# SV601272A-ADC.net
KiCad netlist of a schematic drawn in Altium Designer
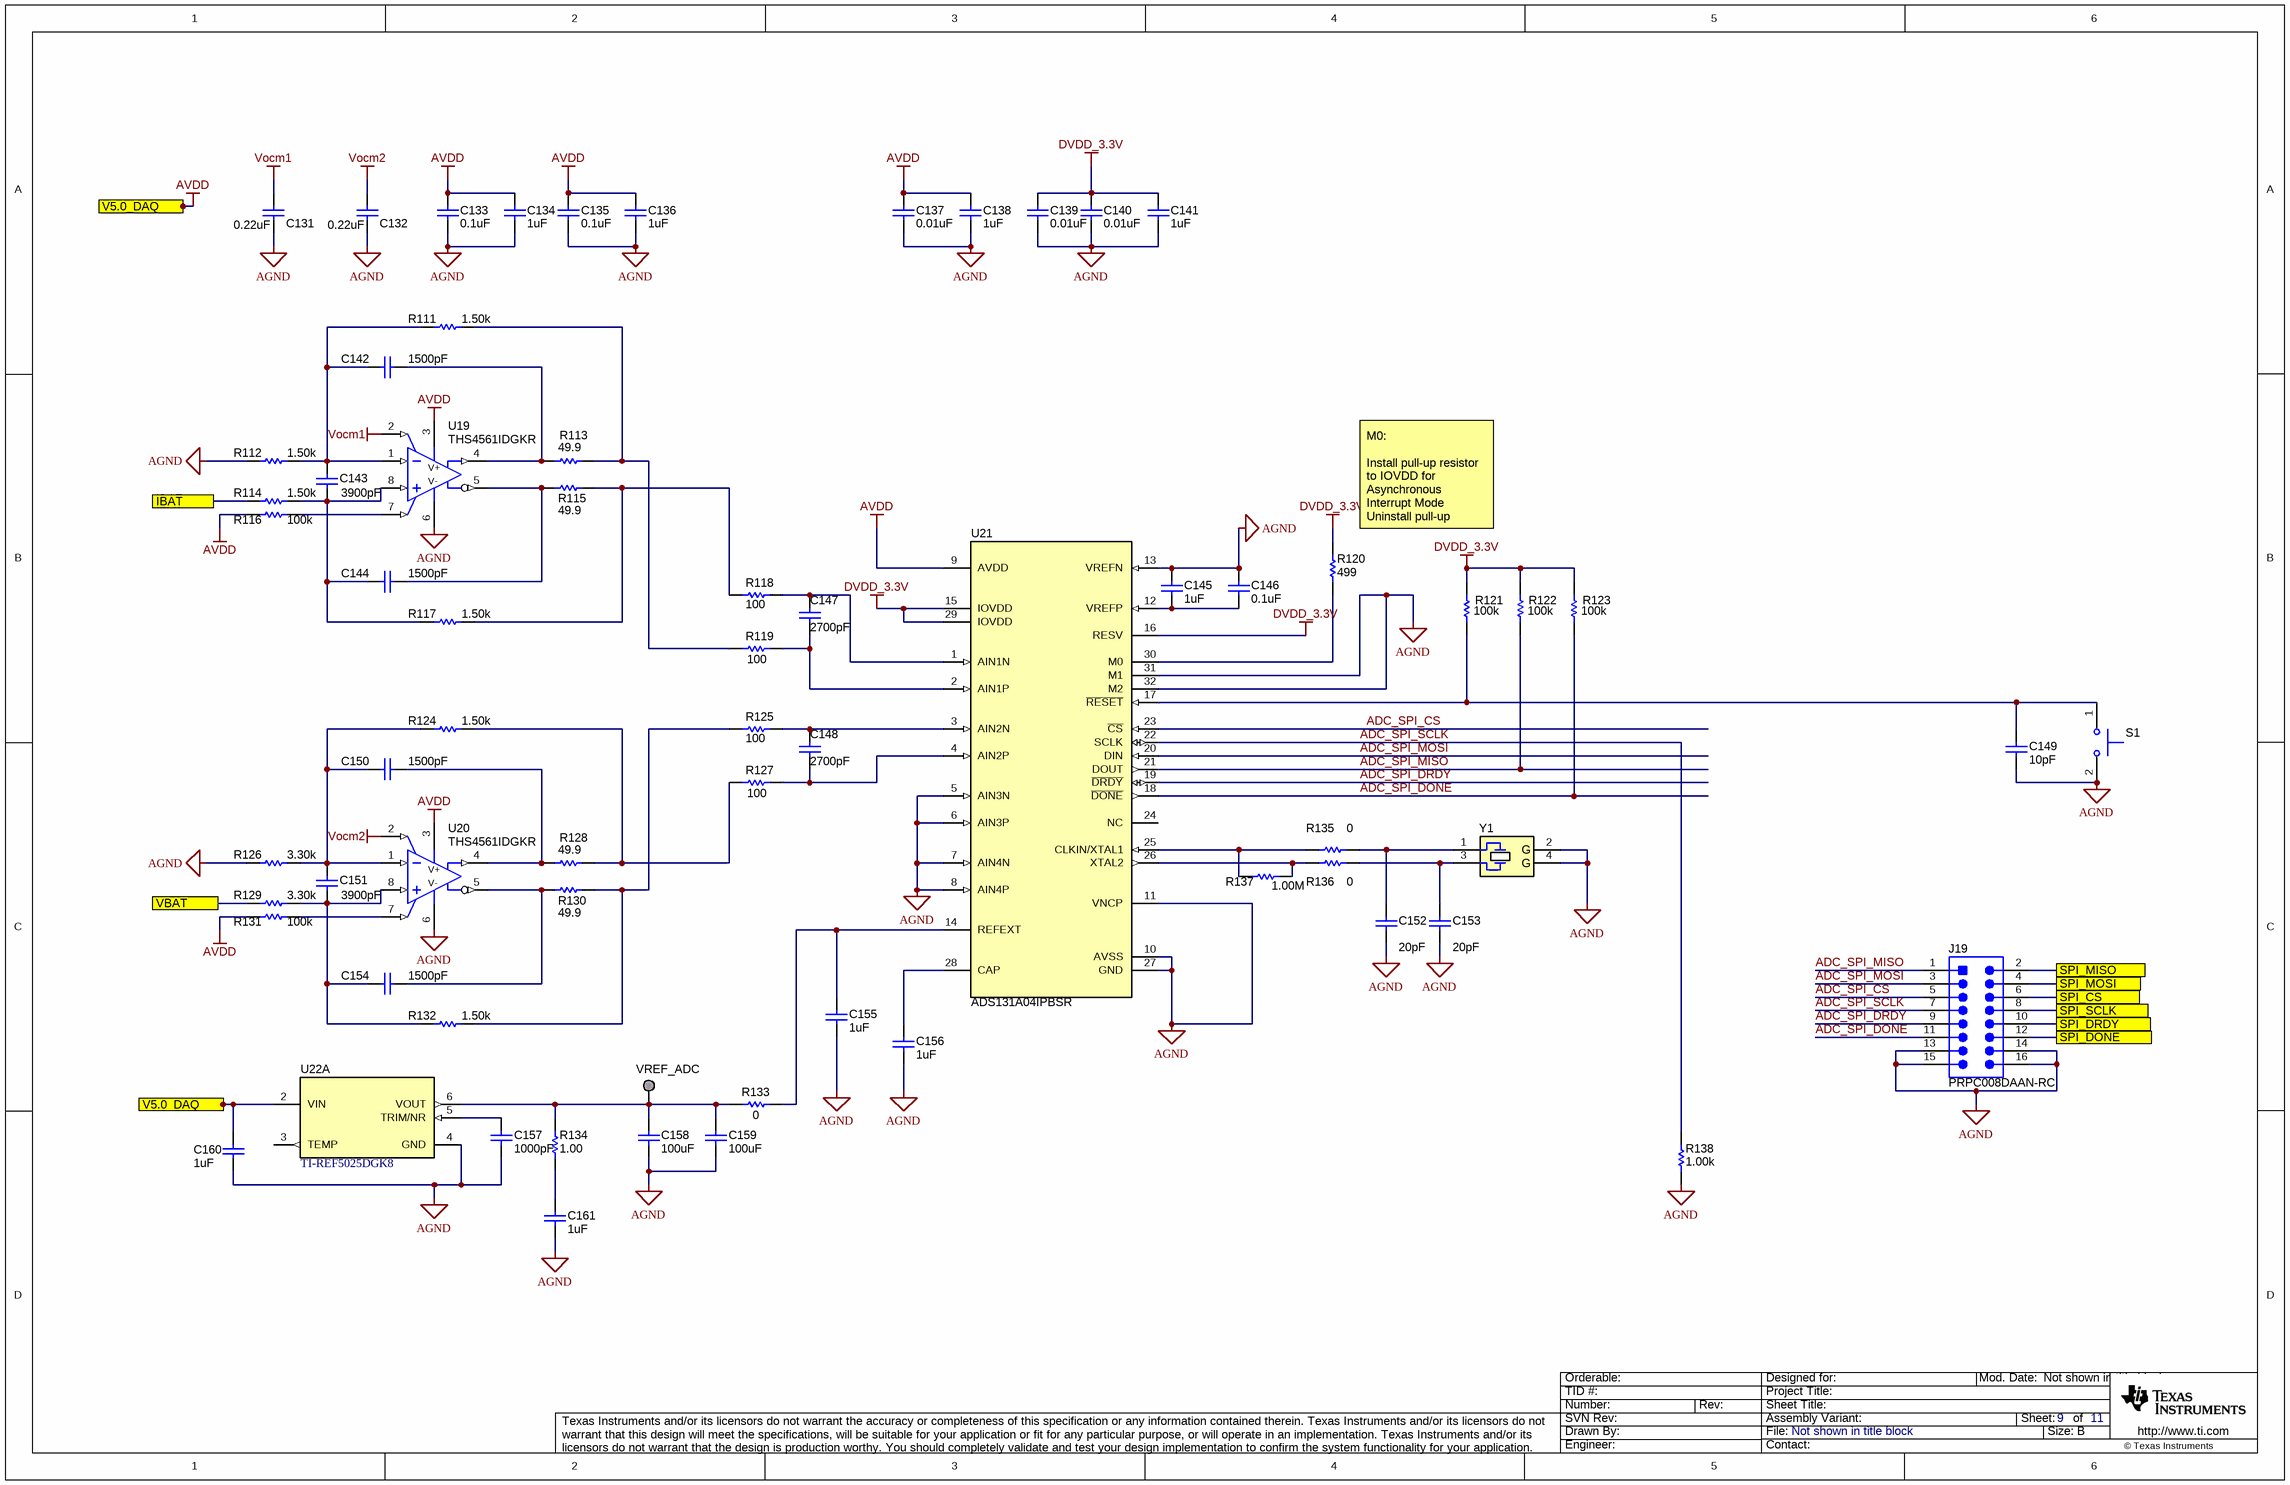
[diagram p0: SV601272A-ADC.SchDoc]

(export (version "E")
  (design (tool "Eeschema 10.0.6"))
  (components
    (comp (ref "C131")
      (value "Capacitor")
      (footprint "0603")
      (description "CAP, CERM, 0.22 uF, 16 V, +/- 10%, X7R, 0603")
      (fields
        (field (name "PARTNUMBER") "C0603C224K4RACTU")
        (field (name "VALUEDISPLAYED") "0.22uF")
        (field (name "MANUFACTURER") "Kemet")
        (field (name "PUBLISHER") "Texas Instruments")
      )
      (libsource (lib "Altium Vault - TI") (part "CMP-0006903-4"))
    )
    (comp (ref "C132")
      (value "Capacitor")
      (footprint "0603")
      (description "CAP, CERM, 0.22 uF, 16 V, +/- 10%, X7R, 0603")
      (fields
        (field (name "PARTNUMBER") "C0603C224K4RACTU")
        (field (name "VALUEDISPLAYED") "0.22uF")
        (field (name "MANUFACTURER") "Kemet")
        (field (name "PUBLISHER") "Texas Instruments")
      )
      (libsource (lib "Altium Vault - TI") (part "CMP-0006903-4"))
    )
    (comp (ref "C133")
      (value "Capacitor")
      (footprint "0603")
      (description "CAP, CERM, 0.1 uF, 25 V, +/- 5%, X7R, 0603")
      (fields
        (field (name "PARTNUMBER") "06033C104JAT2A")
        (field (name "VALUEDISPLAYED") "0.1uF")
        (field (name "MANUFACTURER") "AVX")
        (field (name "PUBLISHER") "Texas Instruments")
      )
      (libsource (lib "Altium Vault - TI") (part "CMP-0006752-5"))
    )
    (comp (ref "C134")
      (value "Capacitor")
      (footprint "0603")
      (description "CAP, CERM, 1 uF, 25 V, +/- 10%, X7R, 0603")
      (fields
        (field (name "PARTNUMBER") "GRM188R71E105KA12D")
        (field (name "VALUEDISPLAYED") "1uF")
        (field (name "MANUFACTURER") "MuRata")
        (field (name "PUBLISHER") "Texas Instruments")
      )
      (libsource (lib "Altium Vault - TI") (part "CMP-0007405-4"))
    )
    (comp (ref "C135")
      (value "Capacitor")
      (footprint "0603")
      (description "CAP, CERM, 0.1 uF, 25 V, +/- 5%, X7R, 0603")
      (fields
        (field (name "PARTNUMBER") "06033C104JAT2A")
        (field (name "VALUEDISPLAYED") "0.1uF")
        (field (name "MANUFACTURER") "AVX")
        (field (name "PUBLISHER") "Texas Instruments")
      )
      (libsource (lib "Altium Vault - TI") (part "CMP-0006752-5"))
    )
    (comp (ref "C136")
      (value "Capacitor")
      (footprint "0603")
      (description "CAP, CERM, 1 uF, 25 V, +/- 10%, X7R, 0603")
      (fields
        (field (name "PARTNUMBER") "GRM188R71E105KA12D")
        (field (name "VALUEDISPLAYED") "1uF")
        (field (name "MANUFACTURER") "MuRata")
        (field (name "PUBLISHER") "Texas Instruments")
      )
      (libsource (lib "Altium Vault - TI") (part "CMP-0007405-4"))
    )
    (comp (ref "C137")
      (value "Capacitor")
      (footprint "0603")
      (description "CAP, CERM, 0.01 uF, 100 V, +/- 10%, X7R, 0603")
      (fields
        (field (name "PARTNUMBER") "06031C103KAT2A")
        (field (name "VALUEDISPLAYED") "0.01uF")
        (field (name "MANUFACTURER") "AVX")
        (field (name "PUBLISHER") "Texas Instruments")
      )
      (libsource (lib "Altium Vault - TI") (part "CMP-0006727-4"))
    )
    (comp (ref "C138")
      (value "Capacitor")
      (footprint "0603")
      (description "CAP, CERM, 1 uF, 25 V, +/- 10%, X7R, 0603")
      (fields
        (field (name "PARTNUMBER") "GRM188R71E105KA12D")
        (field (name "VALUEDISPLAYED") "1uF")
        (field (name "MANUFACTURER") "MuRata")
        (field (name "PUBLISHER") "Texas Instruments")
      )
      (libsource (lib "Altium Vault - TI") (part "CMP-0007405-4"))
    )
    (comp (ref "C139")
      (value "Capacitor")
      (footprint "0603")
      (description "CAP, CERM, 0.01 uF, 100 V, +/- 10%, X7R, 0603")
      (fields
        (field (name "PARTNUMBER") "06031C103KAT2A")
        (field (name "VALUEDISPLAYED") "0.01uF")
        (field (name "MANUFACTURER") "AVX")
        (field (name "PUBLISHER") "Texas Instruments")
      )
      (libsource (lib "Altium Vault - TI") (part "CMP-0006727-4"))
    )
    (comp (ref "C140")
      (value "Capacitor")
      (footprint "0603")
      (description "CAP, CERM, 0.01 uF, 100 V, +/- 10%, X7R, 0603")
      (fields
        (field (name "PARTNUMBER") "06031C103KAT2A")
        (field (name "VALUEDISPLAYED") "0.01uF")
        (field (name "MANUFACTURER") "AVX")
        (field (name "PUBLISHER") "Texas Instruments")
      )
      (libsource (lib "Altium Vault - TI") (part "CMP-0006727-4"))
    )
    (comp (ref "C141")
      (value "Capacitor")
      (footprint "0603")
      (description "CAP, CERM, 1 uF, 25 V, +/- 10%, X7R, 0603")
      (fields
        (field (name "PARTNUMBER") "GRM188R71E105KA12D")
        (field (name "VALUEDISPLAYED") "1uF")
        (field (name "MANUFACTURER") "MuRata")
        (field (name "PUBLISHER") "Texas Instruments")
      )
      (libsource (lib "Altium Vault - TI") (part "CMP-0007405-4"))
    )
    (comp (ref "C142")
      (value "Capacitor")
      (footprint "0603")
      (description "CAP, CERM, 1500 pF, 100 V, +/- 5%, X7R, 0603")
      (fields
        (field (name "PARTNUMBER") "06031C152JAT2A")
        (field (name "VALUEDISPLAYED") "1500pF")
        (field (name "MANUFACTURER") "AVX")
        (field (name "PUBLISHER") "Texas Instruments")
      )
      (libsource (lib "Altium Vault - TI") (part "Capacitor"))
    )
    (comp (ref "C143")
      (value "GRM188R72A392KA01D")
      (footprint "0603")
      (description "CAP, CERM, 3900 pF, 100 V, +/- 10%, X7R, 0603")
      (fields
        (field (name "MANUFACTURER") "MuRata")
        (field (name "VALUEDISPLAYED") "3900pF")
        (field (name "PUBLISHER") "Texas Instruments")
      )
      (libsource (lib "Altium Vault - TI") (part "CMP-0007481-5"))
    )
    (comp (ref "C144")
      (value "Capacitor")
      (footprint "0603")
      (description "CAP, CERM, 1500 pF, 100 V, +/- 5%, X7R, 0603")
      (fields
        (field (name "PARTNUMBER") "06031C152JAT2A")
        (field (name "VALUEDISPLAYED") "1500pF")
        (field (name "MANUFACTURER") "AVX")
        (field (name "PUBLISHER") "Texas Instruments")
      )
      (libsource (lib "Altium Vault - TI") (part "Capacitor"))
    )
    (comp (ref "C145")
      (value "Capacitor")
      (footprint "0603")
      (description "CAP, CERM, 1 uF, 25 V, +/- 10%, X7R, 0603")
      (fields
        (field (name "PARTNUMBER") "GRM188R71E105KA12D")
        (field (name "VALUEDISPLAYED") "1uF")
        (field (name "MANUFACTURER") "MuRata")
        (field (name "PUBLISHER") "Texas Instruments")
      )
      (libsource (lib "Altium Vault - TI") (part "Capacitor"))
    )
    (comp (ref "C146")
      (value "Capacitor")
      (footprint "0603")
      (description "CAP, CERM, 0.1 uF, 25 V, +/- 5%, X7R, 0603")
      (fields
        (field (name "PARTNUMBER") "06033C104JAT2A")
        (field (name "VALUEDISPLAYED") "0.1uF")
        (field (name "MANUFACTURER") "AVX")
        (field (name "PUBLISHER") "Texas Instruments")
      )
      (libsource (lib "Altium Vault - TI") (part "Capacitor"))
    )
    (comp (ref "C147")
      (value "Capacitor")
      (footprint "0603")
      (description "CAP, CERM, 2700 pF, 50 V, +/- 5%, C0G/NP0, 0603")
      (fields
        (field (name "PARTNUMBER") "GRM1885C1H272JA01D")
        (field (name "VALUEDISPLAYED") "2700pF")
        (field (name "MANUFACTURER") "MuRata")
        (field (name "PUBLISHER") "Texas Instruments")
      )
      (libsource (lib "Altium Vault - TI") (part "Capacitor"))
    )
    (comp (ref "C148")
      (value "Capacitor")
      (footprint "0603")
      (description "CAP, CERM, 2700 pF, 50 V, +/- 5%, C0G/NP0, 0603")
      (fields
        (field (name "PARTNUMBER") "GRM1885C1H272JA01D")
        (field (name "VALUEDISPLAYED") "2700pF")
        (field (name "MANUFACTURER") "MuRata")
        (field (name "PUBLISHER") "Texas Instruments")
      )
      (libsource (lib "Altium Vault - TI") (part "Capacitor"))
    )
    (comp (ref "C149")
      (value "Capacitor")
      (footprint "0603")
      (description "CAP, CERM, 10 pF, 50 V, +/- 5%, C0G/NP0, 0603")
      (fields
        (field (name "PARTNUMBER") "06035A100JAT2A")
        (field (name "VALUEDISPLAYED") "10pF")
        (field (name "MANUFACTURER") "AVX")
        (field (name "PUBLISHER") "Texas Instruments")
      )
      (libsource (lib "Altium Vault - TI") (part "Capacitor"))
    )
    (comp (ref "C150")
      (value "Capacitor")
      (footprint "0603")
      (description "CAP, CERM, 1500 pF, 100 V, +/- 5%, X7R, 0603")
      (fields
        (field (name "PARTNUMBER") "06031C152JAT2A")
        (field (name "VALUEDISPLAYED") "1500pF")
        (field (name "MANUFACTURER") "AVX")
        (field (name "PUBLISHER") "Texas Instruments")
      )
      (libsource (lib "Altium Vault - TI") (part "Capacitor"))
    )
    (comp (ref "C151")
      (value "GRM188R72A392KA01D")
      (footprint "0603")
      (description "CAP, CERM, 3900 pF, 100 V, +/- 10%, X7R, 0603")
      (fields
        (field (name "MANUFACTURER") "MuRata")
        (field (name "VALUEDISPLAYED") "3900pF")
        (field (name "PUBLISHER") "Texas Instruments")
      )
      (libsource (lib "Altium Vault - TI") (part "CMP-0007481-5"))
    )
    (comp (ref "C152")
      (value "GRM1885C1H200JA01D")
      (footprint "0603")
      (description "CAP, CERM, 20 pF, 50 V, +/- 5%, C0G/NP0, 0603")
      (fields
        (field (name "MANUFACTURER") "MuRata")
        (field (name "VALUEDISPLAYED") "20pF")
        (field (name "PUBLISHER") "Texas Instruments")
      )
      (libsource (lib "Altium Vault - TI") (part "CMP-0007193-4"))
    )
    (comp (ref "C153")
      (value "GRM1885C1H200JA01D")
      (footprint "0603")
      (description "CAP, CERM, 20 pF, 50 V, +/- 5%, C0G/NP0, 0603")
      (fields
        (field (name "MANUFACTURER") "MuRata")
        (field (name "VALUEDISPLAYED") "20pF")
        (field (name "PUBLISHER") "Texas Instruments")
      )
      (libsource (lib "Altium Vault - TI") (part "CMP-0007193-4"))
    )
    (comp (ref "C154")
      (value "Capacitor")
      (footprint "0603")
      (description "CAP, CERM, 1500 pF, 100 V, +/- 5%, X7R, 0603")
      (fields
        (field (name "PARTNUMBER") "06031C152JAT2A")
        (field (name "VALUEDISPLAYED") "1500pF")
        (field (name "MANUFACTURER") "AVX")
        (field (name "PUBLISHER") "Texas Instruments")
      )
      (libsource (lib "Altium Vault - TI") (part "Capacitor"))
    )
    (comp (ref "C155")
      (value "Capacitor")
      (footprint "0603")
      (description "CAP, CERM, 1 uF, 25 V, +/- 10%, X7R, 0603")
      (fields
        (field (name "PARTNUMBER") "GRM188R71E105KA12D")
        (field (name "VALUEDISPLAYED") "1uF")
        (field (name "MANUFACTURER") "MuRata")
        (field (name "PUBLISHER") "Texas Instruments")
      )
      (libsource (lib "Altium Vault - TI") (part "Capacitor"))
    )
    (comp (ref "C156")
      (value "Capacitor")
      (footprint "0603")
      (description "CAP, CERM, 1 uF, 25 V, +/- 10%, X7R, 0603")
      (fields
        (field (name "PARTNUMBER") "GRM188R71E105KA12D")
        (field (name "VALUEDISPLAYED") "1uF")
        (field (name "MANUFACTURER") "MuRata")
        (field (name "PUBLISHER") "Texas Instruments")
      )
      (libsource (lib "Altium Vault - TI") (part "Capacitor"))
    )
    (comp (ref "C157")
      (value "Capacitor")
      (footprint "0603")
      (description "CAP, CERM, 1000 pF, 100 V, +/- 5%, X7R, 0603")
      (fields
        (field (name "PARTNUMBER") "06031C102JAT2A")
        (field (name "VALUEDISPLAYED") "1000pF")
        (field (name "MANUFACTURER") "AVX")
        (field (name "PUBLISHER") "Texas Instruments")
      )
      (libsource (lib "Altium Vault - TI") (part "Capacitor"))
    )
    (comp (ref "C158")
      (value "Capacitor")
      (footprint "1206_190")
      (description "CAP, CERM, 100 uF, 10 V, +/- 20%, X5R, 1206_190")
      (fields
        (field (name "PARTNUMBER") "C3216X5R1A107M160AC")
        (field (name "VALUEDISPLAYED") "100uF")
        (field (name "MANUFACTURER") "TDK")
        (field (name "PUBLISHER") "Texas Instruments")
      )
      (libsource (lib "Altium Vault - TI") (part "Capacitor"))
    )
    (comp (ref "C159")
      (value "Capacitor")
      (footprint "1206_190")
      (description "CAP, CERM, 100 uF, 10 V, +/- 20%, X5R, 1206_190")
      (fields
        (field (name "PARTNUMBER") "C3216X5R1A107M160AC")
        (field (name "VALUEDISPLAYED") "100uF")
        (field (name "MANUFACTURER") "TDK")
        (field (name "PUBLISHER") "Texas Instruments")
      )
      (libsource (lib "Altium Vault - TI") (part "Capacitor"))
    )
    (comp (ref "C160")
      (value "Capacitor")
      (footprint "0603")
      (description "CAP, CERM, 1 uF, 25 V, +/- 10%, X7R, 0603")
      (fields
        (field (name "PARTNUMBER") "GRM188R71E105KA12D")
        (field (name "VALUEDISPLAYED") "1uF")
        (field (name "MANUFACTURER") "MuRata")
        (field (name "PUBLISHER") "Texas Instruments")
      )
      (libsource (lib "Altium Vault - TI") (part "Capacitor"))
    )
    (comp (ref "C161")
      (value "Capacitor")
      (footprint "0603")
      (description "CAP, CERM, 1 uF, 25 V, +/- 10%, X7R, 0603")
      (fields
        (field (name "PARTNUMBER") "GRM188R71E105KA12D")
        (field (name "VALUEDISPLAYED") "1uF")
        (field (name "MANUFACTURER") "MuRata")
        (field (name "PUBLISHER") "Texas Instruments")
      )
      (libsource (lib "Altium Vault - TI") (part "Capacitor"))
    )
    (comp (ref "J19")
      (value "PRPC008DAAN-RC")
      (footprint "Sullins_xxxC008DAAN")
      (description "Header, 2.54mm, 8x2, Gold, TH")
      (fields
        (field (name "MANUFACTURER") "Sullins Connector Solutions")
        (field (name "PUBLISHER") "Texas Instruments")
      )
      (libsource (lib "Altium Vault - TI") (part "CMP-0054590-1"))
    )
    (comp (ref "R111")
      (value "RC0603FR-071K5L")
      (footprint "0603")
      (description "RES, 1.50 k, 1%, 0.1 W, 0603")
      (fields
        (field (name "MANUFACTURER") "Yageo America")
        (field (name "VALUEDISPLAYED") "1.50k")
        (field (name "PUBLISHER") "Texas Instruments")
      )
      (libsource (lib "Altium Vault - TI") (part "CMP-0022883-3"))
    )
    (comp (ref "R112")
      (value "RC0603FR-071K5L")
      (footprint "0603")
      (description "RES, 1.50 k, 1%, 0.1 W, 0603")
      (fields
        (field (name "MANUFACTURER") "Yageo America")
        (field (name "VALUEDISPLAYED") "1.50k")
        (field (name "PUBLISHER") "Texas Instruments")
      )
      (libsource (lib "Altium Vault - TI") (part "CMP-0022883-3"))
    )
    (comp (ref "R113")
      (value "Resistor")
      (footprint "0603")
      (description "RES, 49.9, 1%, 0.1 W, AEC-Q200 Grade 0, 0603")
      (fields
        (field (name "PARTNUMBER") "CRCW060349R9FKEA")
        (field (name "MANUFACTURER") "Vishay-Dale")
        (field (name "VALUEDISPLAYED") "49.9")
      )
      (libsource (lib "Altium Vault - TI") (part "CMP-0022448-4"))
    )
    (comp (ref "R114")
      (value "RC0603FR-071K5L")
      (footprint "0603")
      (description "RES, 1.50 k, 1%, 0.1 W, 0603")
      (fields
        (field (name "MANUFACTURER") "Yageo America")
        (field (name "VALUEDISPLAYED") "1.50k")
        (field (name "PUBLISHER") "Texas Instruments")
      )
      (libsource (lib "Altium Vault - TI") (part "CMP-0022883-3"))
    )
    (comp (ref "R115")
      (value "Resistor")
      (footprint "0603")
      (description "RES, 49.9, 1%, 0.1 W, AEC-Q200 Grade 0, 0603")
      (fields
        (field (name "PARTNUMBER") "CRCW060349R9FKEA")
        (field (name "MANUFACTURER") "Vishay-Dale")
        (field (name "VALUEDISPLAYED") "49.9")
      )
      (libsource (lib "Altium Vault - TI") (part "CMP-0022448-4"))
    )
    (comp (ref "R116")
      (value "Resistor")
      (footprint "0603")
      (description "RES, 100 k, 1%, 0.1 W, AEC-Q200 Grade 0, 0603")
      (fields
        (field (name "PARTNUMBER") "CRCW0603100KFKEA")
        (field (name "MANUFACTURER") "Vishay-Dale")
        (field (name "VALUEDISPLAYED") "100k")
      )
      (libsource (lib "Altium Vault - TI") (part "CMP-0021990-4"))
    )
    (comp (ref "R117")
      (value "RC0603FR-071K5L")
      (footprint "0603")
      (description "RES, 1.50 k, 1%, 0.1 W, 0603")
      (fields
        (field (name "MANUFACTURER") "Yageo America")
        (field (name "VALUEDISPLAYED") "1.50k")
        (field (name "PUBLISHER") "Texas Instruments")
      )
      (libsource (lib "Altium Vault - TI") (part "CMP-0022883-3"))
    )
    (comp (ref "R118")
      (value "Resistor")
      (footprint "0603")
      (description "RES, 100, 1%, 0.1 W, AEC-Q200 Grade 0, 0603")
      (fields
        (field (name "PARTNUMBER") "CRCW0603100RFKEA")
        (field (name "MANUFACTURER") "Vishay-Dale")
        (field (name "VALUEDISPLAYED") "100")
      )
      (libsource (lib "Altium Vault - TI") (part "CMP-0021991-4"))
    )
    (comp (ref "R119")
      (value "Resistor")
      (footprint "0603")
      (description "RES, 100, 1%, 0.1 W, AEC-Q200 Grade 0, 0603")
      (fields
        (field (name "PARTNUMBER") "CRCW0603100RFKEA")
        (field (name "MANUFACTURER") "Vishay-Dale")
        (field (name "VALUEDISPLAYED") "100")
      )
      (libsource (lib "Altium Vault - TI") (part "CMP-0021991-4"))
    )
    (comp (ref "R120")
      (value "Resistor")
      (footprint "0603")
      (description "RES, 499, 1%, 0.1 W, AEC-Q200 Grade 0, 0603")
      (fields
        (field (name "PARTNUMBER") "CRCW0603499RFKEA")
        (field (name "MANUFACTURER") "Vishay-Dale")
        (field (name "VALUEDISPLAYED") "499")
      )
      (libsource (lib "Altium Vault - TI") (part "CMP-0022446-5"))
    )
    (comp (ref "R121")
      (value "Resistor")
      (footprint "0603")
      (description "RES, 100 k, 1%, 0.1 W, AEC-Q200 Grade 0, 0603")
      (fields
        (field (name "PARTNUMBER") "CRCW0603100KFKEA")
        (field (name "MANUFACTURER") "Vishay-Dale")
        (field (name "VALUEDISPLAYED") "100k")
      )
      (libsource (lib "Altium Vault - TI") (part "CMP-0021990-4"))
    )
    (comp (ref "R122")
      (value "Resistor")
      (footprint "0603")
      (description "RES, 100 k, 1%, 0.1 W, AEC-Q200 Grade 0, 0603")
      (fields
        (field (name "PARTNUMBER") "CRCW0603100KFKEA")
        (field (name "MANUFACTURER") "Vishay-Dale")
        (field (name "VALUEDISPLAYED") "100k")
      )
      (libsource (lib "Altium Vault - TI") (part "CMP-0021990-4"))
    )
    (comp (ref "R123")
      (value "Resistor")
      (footprint "0603")
      (description "RES, 100 k, 1%, 0.1 W, AEC-Q200 Grade 0, 0603")
      (fields
        (field (name "PARTNUMBER") "CRCW0603100KFKEA")
        (field (name "MANUFACTURER") "Vishay-Dale")
        (field (name "VALUEDISPLAYED") "100k")
      )
      (libsource (lib "Altium Vault - TI") (part "CMP-0021990-4"))
    )
    (comp (ref "R124")
      (value "RC0603FR-071K5L")
      (footprint "0603")
      (description "RES, 1.50 k, 1%, 0.1 W, 0603")
      (fields
        (field (name "MANUFACTURER") "Yageo America")
        (field (name "VALUEDISPLAYED") "1.50k")
        (field (name "PUBLISHER") "Texas Instruments")
      )
      (libsource (lib "Altium Vault - TI") (part "CMP-0022883-3"))
    )
    (comp (ref "R125")
      (value "Resistor")
      (footprint "0603")
      (description "RES, 100, 1%, 0.1 W, AEC-Q200 Grade 0, 0603")
      (fields
        (field (name "PARTNUMBER") "CRCW0603100RFKEA")
        (field (name "MANUFACTURER") "Vishay-Dale")
        (field (name "VALUEDISPLAYED") "100")
      )
      (libsource (lib "Altium Vault - TI") (part "CMP-0021991-4"))
    )
    (comp (ref "R126")
      (value "RC0603FR-073K3L")
      (footprint "0603")
      (description "RES, 3.30 k, 1%, 0.1 W, 0603")
      (fields
        (field (name "VALUEDISPLAYED") "3.30k")
        (field (name "MANUFACTURER") "Yageo America")
        (field (name "PUBLISHER") "Texas Instruments")
      )
      (libsource (lib "Altium Vault - TI") (part "Resistor"))
    )
    (comp (ref "R127")
      (value "Resistor")
      (footprint "0603")
      (description "RES, 100, 1%, 0.1 W, AEC-Q200 Grade 0, 0603")
      (fields
        (field (name "PARTNUMBER") "CRCW0603100RFKEA")
        (field (name "MANUFACTURER") "Vishay-Dale")
        (field (name "VALUEDISPLAYED") "100")
      )
      (libsource (lib "Altium Vault - TI") (part "CMP-0021991-4"))
    )
    (comp (ref "R128")
      (value "Resistor")
      (footprint "0603")
      (description "RES, 49.9, 1%, 0.1 W, AEC-Q200 Grade 0, 0603")
      (fields
        (field (name "PARTNUMBER") "CRCW060349R9FKEA")
        (field (name "MANUFACTURER") "Vishay-Dale")
        (field (name "VALUEDISPLAYED") "49.9")
      )
      (libsource (lib "Altium Vault - TI") (part "CMP-0022448-4"))
    )
    (comp (ref "R129")
      (value "RC0603FR-073K3L")
      (footprint "0603")
      (description "RES, 3.30 k, 1%, 0.1 W, 0603")
      (fields
        (field (name "VALUEDISPLAYED") "3.30k")
        (field (name "MANUFACTURER") "Yageo America")
        (field (name "PUBLISHER") "Texas Instruments")
      )
      (libsource (lib "Altium Vault - TI") (part "Resistor"))
    )
    (comp (ref "R130")
      (value "Resistor")
      (footprint "0603")
      (description "RES, 49.9, 1%, 0.1 W, AEC-Q200 Grade 0, 0603")
      (fields
        (field (name "PARTNUMBER") "CRCW060349R9FKEA")
        (field (name "MANUFACTURER") "Vishay-Dale")
        (field (name "VALUEDISPLAYED") "49.9")
      )
      (libsource (lib "Altium Vault - TI") (part "Resistor"))
    )
    (comp (ref "R131")
      (value "Resistor")
      (footprint "0603")
      (description "RES, 100 k, 1%, 0.1 W, AEC-Q200 Grade 0, 0603")
      (fields
        (field (name "PARTNUMBER") "CRCW0603100KFKEA")
        (field (name "MANUFACTURER") "Vishay-Dale")
        (field (name "VALUEDISPLAYED") "100k")
      )
      (libsource (lib "Altium Vault - TI") (part "Resistor"))
    )
    (comp (ref "R132")
      (value "RC0603FR-071K5L")
      (footprint "0603")
      (description "RES, 1.50 k, 1%, 0.1 W, 0603")
      (fields
        (field (name "MANUFACTURER") "Yageo America")
        (field (name "VALUEDISPLAYED") "1.50k")
        (field (name "PUBLISHER") "Texas Instruments")
      )
      (libsource (lib "Altium Vault - TI") (part "Resistor"))
    )
    (comp (ref "R133")
      (value "Resistor")
      (footprint "0603")
      (description "RES, 0, 5%, 0.1 W, 0603")
      (fields
        (field (name "PARTNUMBER") "ERJ-3GEY0R00V")
        (field (name "MANUFACTURER") "Panasonic")
        (field (name "VALUEDISPLAYED") "0")
        (field (name "PUBLISHER") "Texas Instruments")
      )
      (libsource (lib "Altium Vault - TI") (part "Resistor"))
    )
    (comp (ref "R134")
      (value "Resistor")
      (footprint "0603")
      (description "RES, 1.00, 1%, 0.1 W, AEC-Q200 Grade 0, 0603")
      (fields
        (field (name "PARTNUMBER") "CRCW06031R00FKEA")
        (field (name "VALUEDISPLAYED") "1.00")
        (field (name "MANUFACTURER") "Vishay-Dale")
      )
      (libsource (lib "Altium Vault - TI") (part "Resistor"))
    )
    (comp (ref "R135")
      (value "Resistor")
      (footprint "0603")
      (description "RES, 0, 5%, 0.1 W, 0603")
      (fields
        (field (name "PARTNUMBER") "ERJ-3GEY0R00V")
        (field (name "MANUFACTURER") "Panasonic")
        (field (name "VALUEDISPLAYED") "0")
        (field (name "PUBLISHER") "Texas Instruments")
      )
      (libsource (lib "Altium Vault - TI") (part "CMP-0025874-3"))
    )
    (comp (ref "R136")
      (value "Resistor")
      (footprint "0603")
      (description "RES, 0, 5%, 0.1 W, 0603")
      (fields
        (field (name "PARTNUMBER") "ERJ-3GEY0R00V")
        (field (name "MANUFACTURER") "Panasonic")
        (field (name "VALUEDISPLAYED") "0")
        (field (name "PUBLISHER") "Texas Instruments")
      )
      (libsource (lib "Altium Vault - TI") (part "CMP-0025874-3"))
    )
    (comp (ref "R137")
      (value "Resistor")
      (footprint "0603")
      (description "RES, 1.00 M, 1%, 0.1 W, AEC-Q200 Grade 0, 0603")
      (fields
        (field (name "PARTNUMBER") "CRCW06031M00FKEA")
        (field (name "MANUFACTURER") "Vishay-Dale")
        (field (name "VALUEDISPLAYED") "1.00M")
      )
      (libsource (lib "Altium Vault - TI") (part "CMP-0022138-4"))
    )
    (comp (ref "R138")
      (value "Resistor")
      (footprint "0603")
      (description "RES, 1.00 k, 1%, 0.1 W, AEC-Q200 Grade 0, 0603")
      (fields
        (field (name "PARTNUMBER") "CRCW06031K00FKEA")
        (field (name "MANUFACTURER") "Vishay-Dale")
        (field (name "VALUEDISPLAYED") "1.00k")
      )
      (libsource (lib "Altium Vault - TI") (part "CMP-0022109-5"))
    )
    (comp (ref "S1")
      (value "Switch_PushButton")
      (footprint "SW_TL1015AF160QG")
      (description "Switch, Tactile, SPST-NO, 0.05A, 12V, SMT")
      (fields
        (field (name "PARTNUMBER") "TL1015AF160QG")
        (field (name "MANUFACTURER") "E-Switch")
        (field (name "PUBLISHER") "Texas Instruments")
      )
      (libsource (lib "Altium Vault - TI") (part "Switch_PushButton"))
    )
    (comp (ref "U19")
      (value "THS4561IDGKR")
      (footprint "DGK0008A_N")
      (description "Low-Power, High Supply Range, 60-MHz, Fully Differential Amplifier, DGK0008A (VSSOP-8)")
      (fields
        (field (name "ALTERNATE PARTNUMBER") "THS4561IDGKT")
        (field (name "MANUFACTURER") "Texas Instruments")
        (field (name "PARTNUMBER") "THS4561IDGKR")
        (field (name "PUBLISHER") "Texas Instruments")
      )
      (libsource (lib "Altium Vault - TI") (part "CMP-0074888-1"))
    )
    (comp (ref "U20")
      (value "THS4561IDGKR")
      (footprint "DGK0008A_N")
      (description "Low-Power, High Supply Range, 60-MHz, Fully Differential Amplifier, DGK0008A (VSSOP-8)")
      (fields
        (field (name "ALTERNATE PARTNUMBER") "THS4561IDGKT")
        (field (name "MANUFACTURER") "Texas Instruments")
        (field (name "PARTNUMBER") "THS4561IDGKR")
        (field (name "PUBLISHER") "Texas Instruments")
      )
      (libsource (lib "Altium Vault - TI") (part "CMP-0074888-1"))
    )
    (comp (ref "U21")
      (value "ADS131A04IPBSR")
      (footprint "PBS0032A_L")
      (description "24-Bit, 128kSPS, 4-Ch, Simultaneous Sampling, Delta-Sigma ADC, PBS0032A (TQFP-32)")
      (fields
        (field (name "ALTERNATE PARTNUMBER") "ADS131A04IPBS")
        (field (name "PARTNUMBER") "ADS131A04IPBSR")
        (field (name "MANUFACTURER") "Texas Instruments")
        (field (name "PUBLISHER") "Texas Instruments")
      )
      (libsource (lib "Altium Vault - TI") (part "ADS131A04"))
    )
    (comp (ref "U22")
      (value "TI-REF5025DGK8")
      (footprint "DGK0008A_N")
      (fields (field (name "PARTNUMBER") "REF5025IDGKR") (field (name "MANUFACTURER") "Texas Instruments"))
      (libsource (lib "Altium Vault - TI") (part "CMP-0032584-1"))
    )
    (comp (ref "VREF_ADC")
      (value "Pogo Pad")
      (footprint "PogoPad")
      (description "Pad for Pogo Pin Connector")
      (fields (field (name "SYMBOLCREATOR") "codlsc") (field (name "PUBLISHER") "Texas Instruments"))
      (libsource (lib "MiscParts") (part "PogoPad"))
    )
    (comp (ref "Y1")
      (value "XTAL_4P_13_G24")
      (footprint "CTS_407")
      (description "Crystal, 16.384 MHz, 20 pF, SMD")
      (fields
        (field (name "PARTNUMBER") "407F35E016M3840")
        (field (name "MANUFACTURER") "CTS Electrocomponents")
      )
      (libsource (lib "Altium Vault - TI") (part "XTAL_4P_13_G24"))
    )
  )
  (nets
    (net (code "1") (name "/ADC_SPI_CS") (class "Default")
      (node (ref "J19") (pin "5") (pinfunction "5_5") (pintype "passive"))
      (node (ref "U21") (pin "23") (pinfunction "CS_23") (pintype "input"))
    )
    (net (code "2") (name "/ADC_SPI_DONE") (class "Default")
      (node (ref "J19") (pin "11") (pinfunction "11_11") (pintype "passive"))
      (node (ref "R123") (pin "1") (pinfunction "1_1") (pintype "passive"))
      (node (ref "U21") (pin "18") (pinfunction "DONE_18") (pintype "output"))
    )
    (net (code "3") (name "/ADC_SPI_DRDY") (class "Default")
      (node (ref "J19") (pin "9") (pinfunction "9_9") (pintype "passive"))
      (node (ref "U21") (pin "19") (pinfunction "DRDY_19") (pintype "bidirectional"))
    )
    (net (code "4") (name "/ADC_SPI_MISO") (class "Default")
      (node (ref "J19") (pin "1") (pinfunction "1_1") (pintype "passive"))
      (node (ref "R122") (pin "1") (pinfunction "1_1") (pintype "passive"))
      (node (ref "U21") (pin "21") (pinfunction "DOUT_21") (pintype "output"))
    )
    (net (code "5") (name "/ADC_SPI_MOSI") (class "Default")
      (node (ref "J19") (pin "3") (pinfunction "3_3") (pintype "passive"))
      (node (ref "U21") (pin "20") (pinfunction "DIN_20") (pintype "input"))
    )
    (net (code "6") (name "/ADC_SPI_SCLK") (class "Default")
      (node (ref "J19") (pin "7") (pinfunction "7_7") (pintype "passive"))
      (node (ref "R138") (pin "2") (pinfunction "2_2") (pintype "passive"))
      (node (ref "U21") (pin "22") (pinfunction "SCLK_22") (pintype "bidirectional"))
    )
    (net (code "7") (name "/IBAT") (class "Default")
      (node (ref "R114") (pin "1") (pinfunction "1_1") (pintype "passive"))
    )
    (net (code "8") (name "/SPI_CS") (class "Default")
      (node (ref "J19") (pin "6") (pinfunction "6_6") (pintype "passive"))
    )
    (net (code "9") (name "/SPI_DONE") (class "Default")
      (node (ref "J19") (pin "12") (pinfunction "12_12") (pintype "passive"))
    )
    (net (code "10") (name "/SPI_DRDY") (class "Default")
      (node (ref "J19") (pin "10") (pinfunction "10_10") (pintype "passive"))
    )
    (net (code "11") (name "/SPI_MISO") (class "Default")
      (node (ref "J19") (pin "2") (pinfunction "2_2") (pintype "passive"))
    )
    (net (code "12") (name "/SPI_MOSI") (class "Default")
      (node (ref "J19") (pin "4") (pinfunction "4_4") (pintype "passive"))
    )
    (net (code "13") (name "/SPI_SCLK") (class "Default")
      (node (ref "J19") (pin "8") (pinfunction "8_8") (pintype "passive"))
    )
    (net (code "14") (name "/VBAT") (class "Default")
      (node (ref "R129") (pin "1") (pinfunction "1_1") (pintype "passive"))
    )
    (net (code "15") (name "AGND") (class "Default")
      (node (ref "C131") (pin "2") (pinfunction "2_2") (pintype "passive"))
      (node (ref "C132") (pin "2") (pinfunction "2_2") (pintype "passive"))
      (node (ref "C133") (pin "2") (pinfunction "2_2") (pintype "passive"))
      (node (ref "C134") (pin "2") (pinfunction "2_2") (pintype "passive"))
      (node (ref "C135") (pin "2") (pinfunction "2_2") (pintype "passive"))
      (node (ref "C136") (pin "2") (pinfunction "2_2") (pintype "passive"))
      (node (ref "C137") (pin "2") (pinfunction "2_2") (pintype "passive"))
      (node (ref "C138") (pin "2") (pinfunction "2_2") (pintype "passive"))
      (node (ref "C139") (pin "2") (pinfunction "2_2") (pintype "passive"))
      (node (ref "C140") (pin "2") (pinfunction "2_2") (pintype "passive"))
      (node (ref "C141") (pin "2") (pinfunction "2_2") (pintype "passive"))
      (node (ref "C145") (pin "1") (pinfunction "1_1") (pintype "passive"))
      (node (ref "C146") (pin "1") (pinfunction "1_1") (pintype "passive"))
      (node (ref "C149") (pin "1") (pinfunction "1_1") (pintype "passive"))
      (node (ref "C152") (pin "2") (pinfunction "2_2") (pintype "passive"))
      (node (ref "C153") (pin "2") (pinfunction "2_2") (pintype "passive"))
      (node (ref "C155") (pin "2") (pinfunction "2_2") (pintype "passive"))
      (node (ref "C156") (pin "2") (pinfunction "2_2") (pintype "passive"))
      (node (ref "C157") (pin "2") (pinfunction "2_2") (pintype "passive"))
      (node (ref "C158") (pin "2") (pinfunction "2_2") (pintype "passive"))
      (node (ref "C159") (pin "2") (pinfunction "2_2") (pintype "passive"))
      (node (ref "C160") (pin "2") (pinfunction "2_2") (pintype "passive"))
      (node (ref "C161") (pin "2") (pinfunction "2_2") (pintype "passive"))
      (node (ref "J19") (pin "13") (pinfunction "13_13") (pintype "passive"))
      (node (ref "J19") (pin "14") (pinfunction "14_14") (pintype "passive"))
      (node (ref "J19") (pin "15") (pinfunction "15_15") (pintype "passive"))
      (node (ref "J19") (pin "16") (pinfunction "16_16") (pintype "passive"))
      (node (ref "R112") (pin "1") (pinfunction "1_1") (pintype "passive"))
      (node (ref "R126") (pin "1") (pinfunction "1_1") (pintype "passive"))
      (node (ref "R138") (pin "1") (pinfunction "1_1") (pintype "passive"))
      (node (ref "S1") (pin "2") (pinfunction "2_2") (pintype "passive"))
      (node (ref "U19") (pin "6") (pinfunction "VS-_6") (pintype "power_in"))
      (node (ref "U20") (pin "6") (pinfunction "VS-_6") (pintype "power_in"))
      (node (ref "U21") (pin "10") (pinfunction "AVSS_10") (pintype "power_in"))
      (node (ref "U21") (pin "11") (pinfunction "VNCP_11") (pintype "power_in"))
      (node (ref "U21") (pin "13") (pinfunction "VREFN_13") (pintype "input"))
      (node (ref "U21") (pin "27") (pinfunction "GND_27") (pintype "power_in"))
      (node (ref "U21") (pin "31") (pinfunction "M1_31") (pintype "passive"))
      (node (ref "U21") (pin "32") (pinfunction "M2_32") (pintype "passive"))
      (node (ref "U21") (pin "5") (pinfunction "AIN3N_5") (pintype "input"))
      (node (ref "U21") (pin "6") (pinfunction "AIN3P_6") (pintype "input"))
      (node (ref "U21") (pin "7") (pinfunction "AIN4N_7") (pintype "input"))
      (node (ref "U21") (pin "8") (pinfunction "AIN4P_8") (pintype "input"))
      (node (ref "U22") (pin "4") (pinfunction "GND_4") (pintype "power_in"))
      (node (ref "Y1") (pin "2") (pinfunction "GND_2") (pintype "power_in"))
      (node (ref "Y1") (pin "4") (pinfunction "GND_4") (pintype "power_in"))
    )
    (net (code "16") (name "AVDD") (class "Default")
      (node (ref "C133") (pin "1") (pinfunction "1_1") (pintype "passive"))
      (node (ref "C134") (pin "1") (pinfunction "1_1") (pintype "passive"))
      (node (ref "C135") (pin "1") (pinfunction "1_1") (pintype "passive"))
      (node (ref "C136") (pin "1") (pinfunction "1_1") (pintype "passive"))
      (node (ref "C137") (pin "1") (pinfunction "1_1") (pintype "passive"))
      (node (ref "C138") (pin "1") (pinfunction "1_1") (pintype "passive"))
      (node (ref "C160") (pin "1") (pinfunction "1_1") (pintype "passive"))
      (node (ref "R116") (pin "2") (pinfunction "2_2") (pintype "passive"))
      (node (ref "R131") (pin "2") (pinfunction "2_2") (pintype "passive"))
      (node (ref "U19") (pin "3") (pinfunction "VS+_3") (pintype "power_in"))
      (node (ref "U20") (pin "3") (pinfunction "VS+_3") (pintype "power_in"))
      (node (ref "U21") (pin "9") (pinfunction "AVDD_9") (pintype "power_in"))
      (node (ref "U22") (pin "2") (pinfunction "VIN_2") (pintype "power_in"))
    )
    (net (code "17") (name "DVDD_3.3V") (class "Default")
      (node (ref "C139") (pin "1") (pinfunction "1_1") (pintype "passive"))
      (node (ref "C140") (pin "1") (pinfunction "1_1") (pintype "passive"))
      (node (ref "C141") (pin "1") (pinfunction "1_1") (pintype "passive"))
      (node (ref "R120") (pin "2") (pinfunction "2_2") (pintype "passive"))
      (node (ref "R121") (pin "2") (pinfunction "2_2") (pintype "passive"))
      (node (ref "R122") (pin "2") (pinfunction "2_2") (pintype "passive"))
      (node (ref "R123") (pin "2") (pinfunction "2_2") (pintype "passive"))
      (node (ref "U21") (pin "15") (pinfunction "IOVDD_15") (pintype "power_in"))
      (node (ref "U21") (pin "16") (pinfunction "RESV_16") (pintype "passive"))
      (node (ref "U21") (pin "29") (pinfunction "IOVDD_29") (pintype "power_in"))
    )
    (net (code "18") (name "Net-(C152-Pad1)") (class "Default")
      (node (ref "C152") (pin "1") (pinfunction "1_1") (pintype "passive"))
      (node (ref "R135") (pin "2") (pinfunction "2_2") (pintype "passive"))
      (node (ref "Y1") (pin "1") (pinfunction "1_1") (pintype "passive"))
    )
    (net (code "19") (name "Net-(C153-Pad1)") (class "Default")
      (node (ref "C153") (pin "1") (pinfunction "1_1") (pintype "passive"))
      (node (ref "R136") (pin "1") (pinfunction "1_1") (pintype "passive"))
      (node (ref "Y1") (pin "3") (pinfunction "3_3") (pintype "passive"))
    )
    (net (code "20") (name "Net-(C161-Pad1)") (class "Default")
      (node (ref "C161") (pin "1") (pinfunction "1_1") (pintype "passive"))
      (node (ref "R134") (pin "1") (pinfunction "1_1") (pintype "passive"))
    )
    (net (code "21") (name "Net-(R111-Pad2)") (class "Default")
      (node (ref "R111") (pin "2") (pinfunction "2_2") (pintype "passive"))
      (node (ref "R113") (pin "2") (pinfunction "2_2") (pintype "passive"))
      (node (ref "R119") (pin "1") (pinfunction "1_1") (pintype "passive"))
    )
    (net (code "22") (name "Net-(R115-Pad2)") (class "Default")
      (node (ref "R115") (pin "2") (pinfunction "2_2") (pintype "passive"))
      (node (ref "R117") (pin "2") (pinfunction "2_2") (pintype "passive"))
      (node (ref "R118") (pin "1") (pinfunction "1_1") (pintype "passive"))
    )
    (net (code "23") (name "Net-(R124-Pad2)") (class "Default")
      (node (ref "R124") (pin "2") (pinfunction "2_2") (pintype "passive"))
      (node (ref "R127") (pin "1") (pinfunction "1_1") (pintype "passive"))
      (node (ref "R128") (pin "2") (pinfunction "2_2") (pintype "passive"))
    )
    (net (code "24") (name "Net-(R125-Pad1)") (class "Default")
      (node (ref "R125") (pin "1") (pinfunction "1_1") (pintype "passive"))
      (node (ref "R130") (pin "2") (pinfunction "2_2") (pintype "passive"))
      (node (ref "R132") (pin "2") (pinfunction "2_2") (pintype "passive"))
    )
    (net (code "25") (name "Net-(U19-VIN+)") (class "Default")
      (node (ref "C143") (pin "2") (pinfunction "2_2") (pintype "passive"))
      (node (ref "C144") (pin "1") (pinfunction "1_1") (pintype "passive"))
      (node (ref "R114") (pin "2") (pinfunction "2_2") (pintype "passive"))
      (node (ref "R117") (pin "1") (pinfunction "1_1") (pintype "passive"))
      (node (ref "U19") (pin "8") (pinfunction "VIN+_8") (pintype "input"))
    )
    (net (code "26") (name "Net-(U19-VIN-)") (class "Default")
      (node (ref "C142") (pin "1") (pinfunction "1_1") (pintype "passive"))
      (node (ref "C143") (pin "1") (pinfunction "1_1") (pintype "passive"))
      (node (ref "R111") (pin "1") (pinfunction "1_1") (pintype "passive"))
      (node (ref "R112") (pin "2") (pinfunction "2_2") (pintype "passive"))
      (node (ref "U19") (pin "1") (pinfunction "VIN-_1") (pintype "input"))
    )
    (net (code "27") (name "Net-(U19-VOUT+)") (class "Default")
      (node (ref "C142") (pin "2") (pinfunction "2_2") (pintype "passive"))
      (node (ref "R113") (pin "1") (pinfunction "1_1") (pintype "passive"))
      (node (ref "U19") (pin "4") (pinfunction "VOUT+_4") (pintype "output"))
    )
    (net (code "28") (name "Net-(U19-VOUT-)") (class "Default")
      (node (ref "C144") (pin "2") (pinfunction "2_2") (pintype "passive"))
      (node (ref "R115") (pin "1") (pinfunction "1_1") (pintype "passive"))
      (node (ref "U19") (pin "5") (pinfunction "VOUT-_5") (pintype "output"))
    )
    (net (code "29") (name "Net-(U19-~{PD})") (class "Default")
      (node (ref "R116") (pin "1") (pinfunction "1_1") (pintype "passive"))
      (node (ref "U19") (pin "7") (pinfunction "~{PD}_7") (pintype "input"))
    )
    (net (code "30") (name "Net-(U20-VIN+)") (class "Default")
      (node (ref "C151") (pin "2") (pinfunction "2_2") (pintype "passive"))
      (node (ref "C154") (pin "1") (pinfunction "1_1") (pintype "passive"))
      (node (ref "R129") (pin "2") (pinfunction "2_2") (pintype "passive"))
      (node (ref "R132") (pin "1") (pinfunction "1_1") (pintype "passive"))
      (node (ref "U20") (pin "8") (pinfunction "VIN+_8") (pintype "input"))
    )
    (net (code "31") (name "Net-(U20-VIN-)") (class "Default")
      (node (ref "C150") (pin "1") (pinfunction "1_1") (pintype "passive"))
      (node (ref "C151") (pin "1") (pinfunction "1_1") (pintype "passive"))
      (node (ref "R124") (pin "1") (pinfunction "1_1") (pintype "passive"))
      (node (ref "R126") (pin "2") (pinfunction "2_2") (pintype "passive"))
      (node (ref "U20") (pin "1") (pinfunction "VIN-_1") (pintype "input"))
    )
    (net (code "32") (name "Net-(U20-VOUT+)") (class "Default")
      (node (ref "C150") (pin "2") (pinfunction "2_2") (pintype "passive"))
      (node (ref "R128") (pin "1") (pinfunction "1_1") (pintype "passive"))
      (node (ref "U20") (pin "4") (pinfunction "VOUT+_4") (pintype "output"))
    )
    (net (code "33") (name "Net-(U20-VOUT-)") (class "Default")
      (node (ref "C154") (pin "2") (pinfunction "2_2") (pintype "passive"))
      (node (ref "R130") (pin "1") (pinfunction "1_1") (pintype "passive"))
      (node (ref "U20") (pin "5") (pinfunction "VOUT-_5") (pintype "output"))
    )
    (net (code "34") (name "Net-(U20-~{PD})") (class "Default")
      (node (ref "R131") (pin "1") (pinfunction "1_1") (pintype "passive"))
      (node (ref "U20") (pin "7") (pinfunction "~{PD}_7") (pintype "input"))
    )
    (net (code "35") (name "Net-(U21-AIN1N)") (class "Default")
      (node (ref "C147") (pin "1") (pinfunction "1_1") (pintype "passive"))
      (node (ref "R118") (pin "2") (pinfunction "2_2") (pintype "passive"))
      (node (ref "U21") (pin "1") (pinfunction "AIN1N_1") (pintype "input"))
    )
    (net (code "36") (name "Net-(U21-AIN1P)") (class "Default")
      (node (ref "C147") (pin "2") (pinfunction "2_2") (pintype "passive"))
      (node (ref "R119") (pin "2") (pinfunction "2_2") (pintype "passive"))
      (node (ref "U21") (pin "2") (pinfunction "AIN1P_2") (pintype "input"))
    )
    (net (code "37") (name "Net-(U21-AIN2N)") (class "Default")
      (node (ref "C148") (pin "1") (pinfunction "1_1") (pintype "passive"))
      (node (ref "R125") (pin "2") (pinfunction "2_2") (pintype "passive"))
      (node (ref "U21") (pin "3") (pinfunction "AIN2N_3") (pintype "input"))
    )
    (net (code "38") (name "Net-(U21-AIN2P)") (class "Default")
      (node (ref "C148") (pin "2") (pinfunction "2_2") (pintype "passive"))
      (node (ref "R127") (pin "2") (pinfunction "2_2") (pintype "passive"))
      (node (ref "U21") (pin "4") (pinfunction "AIN2P_4") (pintype "input"))
    )
    (net (code "39") (name "Net-(U21-CAP)") (class "Default")
      (node (ref "C156") (pin "1") (pinfunction "1_1") (pintype "passive"))
      (node (ref "U21") (pin "28") (pinfunction "CAP_28") (pintype "passive"))
    )
    (net (code "40") (name "Net-(U21-CLKIN{slash}XTAL1)") (class "Default")
      (node (ref "R135") (pin "1") (pinfunction "1_1") (pintype "passive"))
      (node (ref "R137") (pin "2") (pinfunction "2_2") (pintype "passive"))
      (node (ref "U21") (pin "25") (pinfunction "CLKIN/XTAL1_25") (pintype "input"))
    )
    (net (code "41") (name "Net-(U21-M0)") (class "Default")
      (node (ref "R120") (pin "1") (pinfunction "1_1") (pintype "passive"))
      (node (ref "U21") (pin "30") (pinfunction "M0_30") (pintype "passive"))
    )
    (net (code "42") (name "Net-(U21-REFEXT)") (class "Default")
      (node (ref "C155") (pin "1") (pinfunction "1_1") (pintype "passive"))
      (node (ref "R133") (pin "2") (pinfunction "2_2") (pintype "passive"))
      (node (ref "U21") (pin "14") (pinfunction "REFEXT_14") (pintype "passive"))
    )
    (net (code "43") (name "Net-(U21-RESET)") (class "Default")
      (node (ref "C149") (pin "2") (pinfunction "2_2") (pintype "passive"))
      (node (ref "R121") (pin "1") (pinfunction "1_1") (pintype "passive"))
      (node (ref "S1") (pin "1") (pinfunction "1_1") (pintype "passive"))
      (node (ref "U21") (pin "17") (pinfunction "RESET_17") (pintype "input"))
    )
    (net (code "44") (name "Net-(U21-VREFP)") (class "Default")
      (node (ref "C145") (pin "2") (pinfunction "2_2") (pintype "passive"))
      (node (ref "C146") (pin "2") (pinfunction "2_2") (pintype "passive"))
      (node (ref "U21") (pin "12") (pinfunction "VREFP_12") (pintype "input"))
    )
    (net (code "45") (name "Net-(U21-XTAL2)") (class "Default")
      (node (ref "R136") (pin "2") (pinfunction "2_2") (pintype "passive"))
      (node (ref "R137") (pin "1") (pinfunction "1_1") (pintype "passive"))
      (node (ref "U21") (pin "26") (pinfunction "XTAL2_26") (pintype "output"))
    )
    (net (code "46") (name "Net-(U22A-TRIM{slash}NR)") (class "Default")
      (node (ref "C157") (pin "1") (pinfunction "1_1") (pintype "passive"))
      (node (ref "U22") (pin "5") (pinfunction "TRIM/NR_5") (pintype "input"))
    )
    (net (code "47") (name "Net-(U22A-VOUT)") (class "Default")
      (node (ref "C158") (pin "1") (pinfunction "1_1") (pintype "passive"))
      (node (ref "C159") (pin "1") (pinfunction "1_1") (pintype "passive"))
      (node (ref "R133") (pin "1") (pinfunction "1_1") (pintype "passive"))
      (node (ref "R134") (pin "2") (pinfunction "2_2") (pintype "passive"))
      (node (ref "U22") (pin "6") (pinfunction "VOUT_6") (pintype "output"))
      (node (ref "VREF_ADC") (pin "1") (pintype "passive"))
    )
    (net (code "48") (name "Vocm1") (class "Default")
      (node (ref "C131") (pin "1") (pinfunction "1_1") (pintype "passive"))
      (node (ref "U19") (pin "2") (pinfunction "VOCM_2") (pintype "input"))
    )
    (net (code "49") (name "Vocm2") (class "Default")
      (node (ref "C132") (pin "1") (pinfunction "1_1") (pintype "passive"))
      (node (ref "U20") (pin "2") (pinfunction "VOCM_2") (pintype "input"))
    )
    (net (code "50") (name "unconnected-(U21-NC-Pad24)") (class "Default")
      (node (ref "U21") (pin "24") (pinfunction "NC_24") (pintype "passive"))
    )
    (net (code "51") (name "unconnected-(U22A-TEMP-Pad3)") (class "Default")
      (node (ref "U22") (pin "3") (pinfunction "TEMP_3") (pintype "output"))
    )
  )
)
